# SY_HR08_MCU_TOP_V1_1.net
KiCad netlist of a schematic drawn in Altium Designer
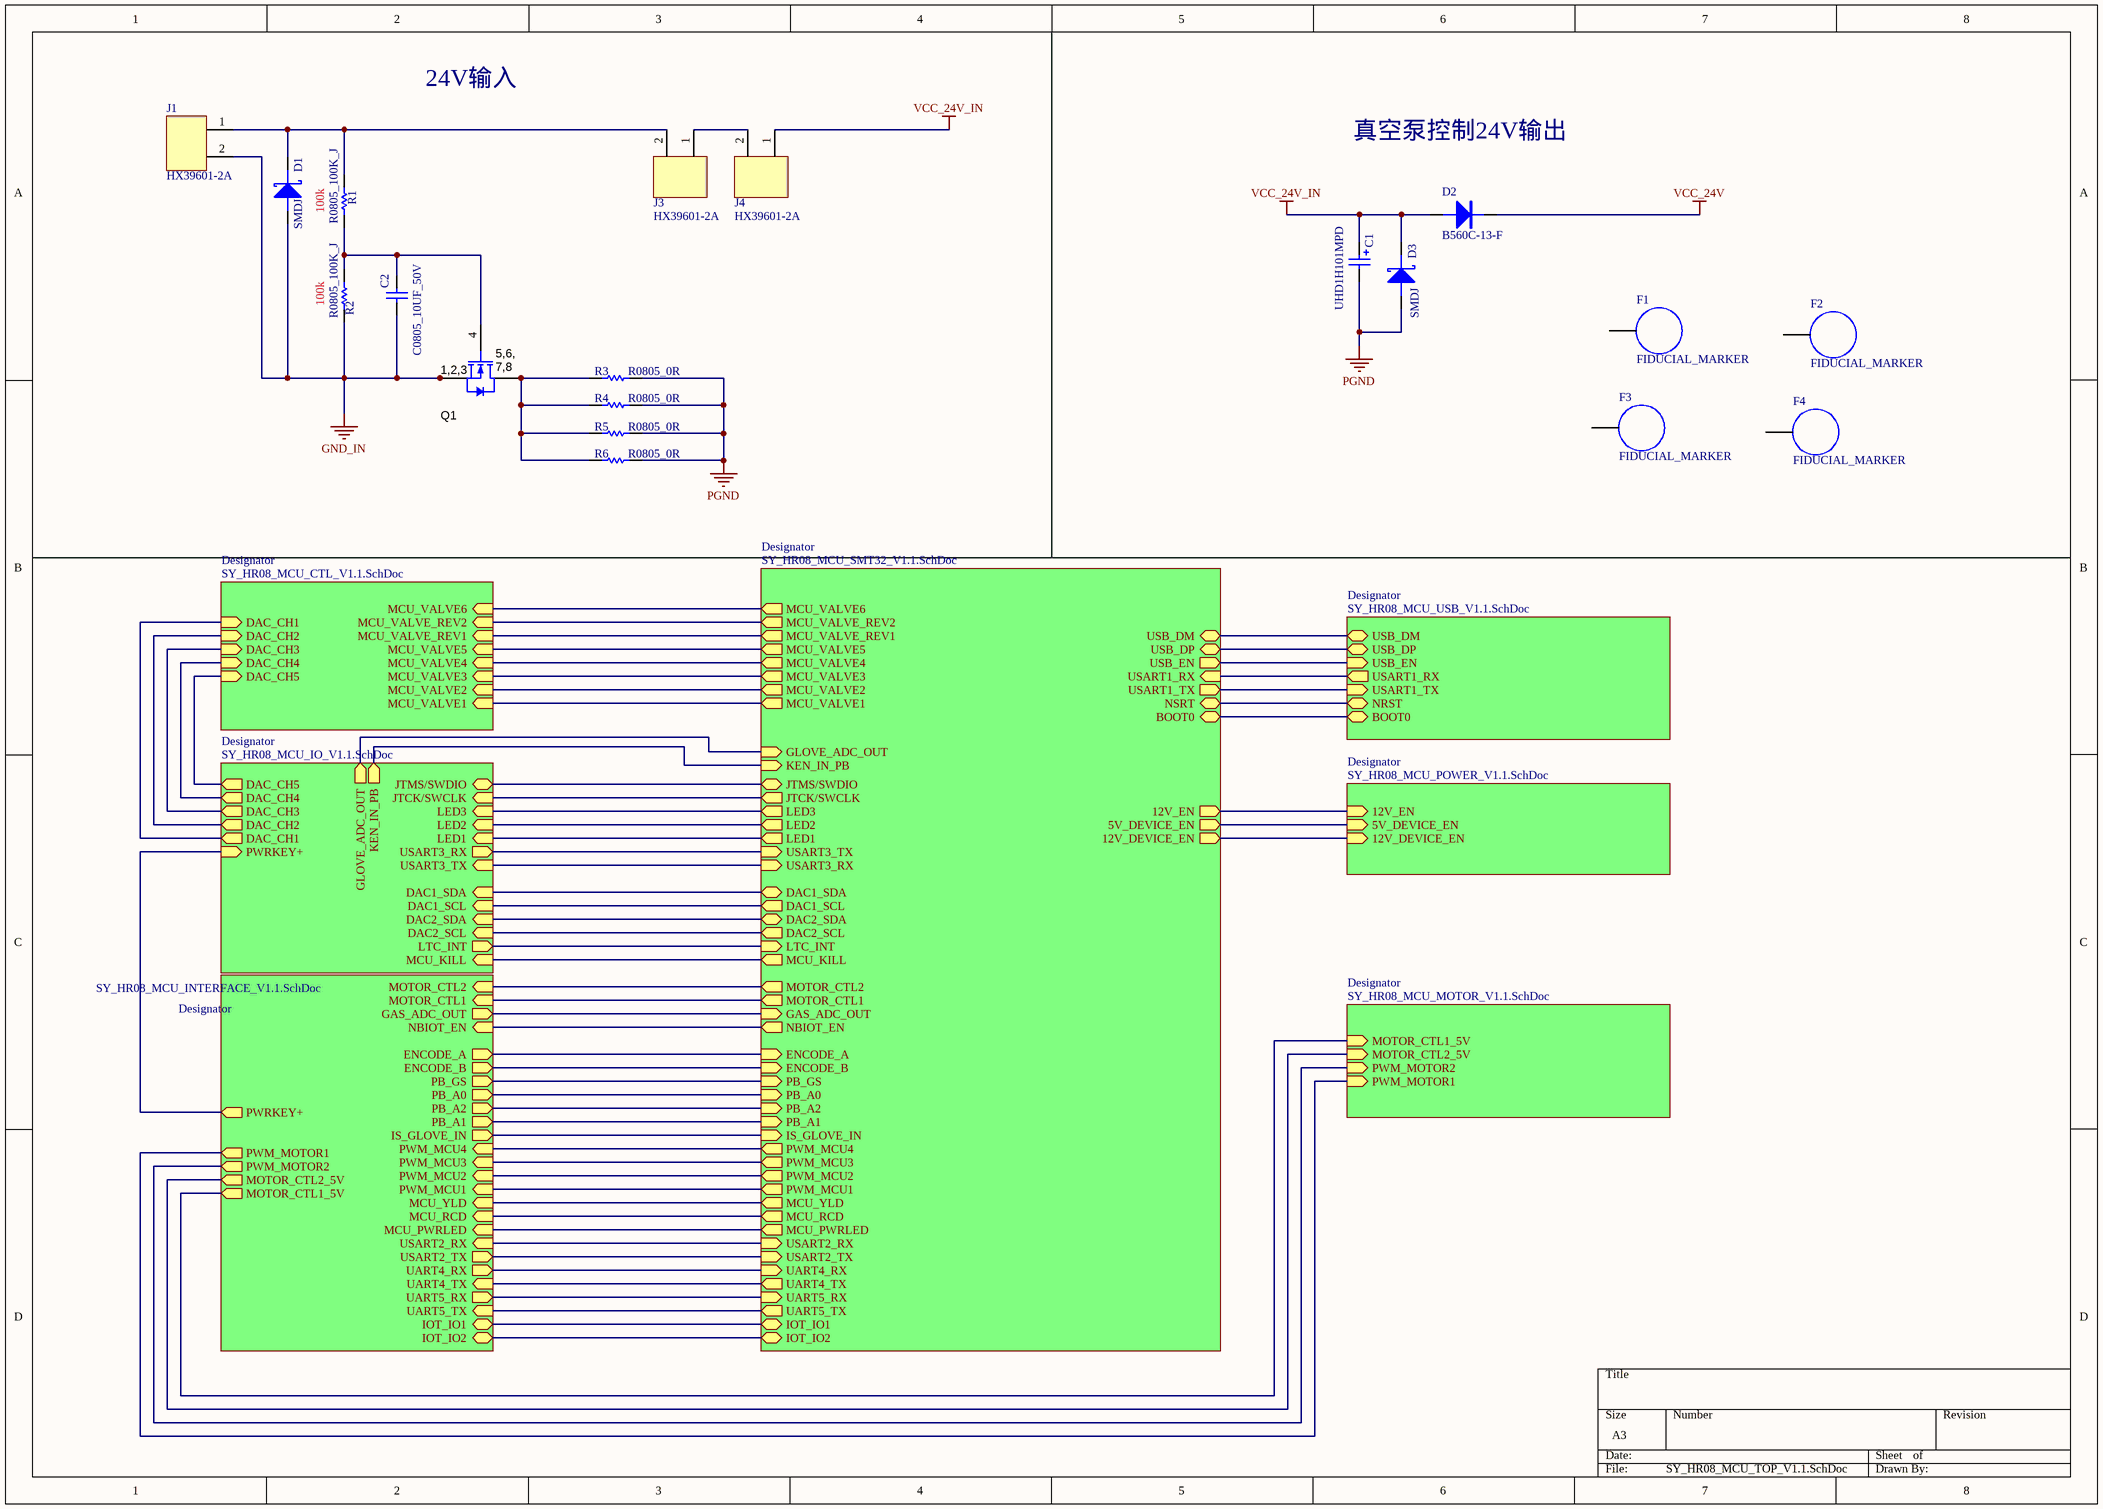
[diagram p0: SY_HR08_MCU_TOP_V1.1.SchDoc]

(export (version "E")
  (design (tool "Eeschema 10.0.6"))
  (components
    (comp (ref "C1")
      (value "UHD1H101MPD")
      (footprint "UHD1H101MPD")
      (description "铝电解电容_100uF_80115_50V_20%")
      (fields (field (name "MANUFACTURER") "nichicon"))
      (libsource (lib "zhangky_sch") (part "UHD1H101MPD"))
    )
    (comp (ref "C2")
      (value "C0805_10UF_50V")
      (footprint "CAP0805-B")
      (description "电容_10uF_0805_X5R_10V_K")
      (libsource (lib "zhangky_sch") (part "C0805_10UF_10V"))
    )
    (comp (ref "D1")
      (value "SMDJ")
      (footprint "SMDJ")
      (description "防浪涌TVS VRWM=30V VBRmin=33.3 VC=48.4 IPP=62A")
      (libsource (lib "zhangky_sch") (part "SMDJ"))
    )
    (comp (ref "D2")
      (value "B560C-13-F")
      (footprint "B540C-13-F")
      (description "肖特基二极管_5A_SMC")
      (libsource (lib "zhangky_sch") (part "B560C-13-F"))
    )
    (comp (ref "D3")
      (value "SMDJ")
      (footprint "SMDJ")
      (description "防浪涌TVS VRWM=30V VBRmin=33.3 VC=48.4 IPP=62A")
      (libsource (lib "zhangky_sch") (part "SMDJ"))
    )
    (comp (ref "F1")
      (value "FIDUCIAL_MARKER")
      (footprint "FIDUCIAL_WITHPASTE")
      (libsource (lib "zhangky_sch") (part "FIDUCIAL_MARKER"))
    )
    (comp (ref "F2")
      (value "FIDUCIAL_MARKER")
      (footprint "FIDUCIAL_WITHPASTE")
      (libsource (lib "zhangky_sch") (part "FIDUCIAL_MARKER"))
    )
    (comp (ref "F3")
      (value "FIDUCIAL_MARKER")
      (footprint "FIDUCIAL_WITHPASTE")
      (libsource (lib "zhangky_sch") (part "FIDUCIAL_MARKER"))
    )
    (comp (ref "F4")
      (value "FIDUCIAL_MARKER")
      (footprint "FIDUCIAL_WITHPASTE")
      (libsource (lib "zhangky_sch") (part "FIDUCIAL_MARKER"))
    )
    (comp (ref "J1")
      (value "HX39601-2A")
      (footprint "HX39601-2A")
      (description "HX39601-2A 3.96mm")
      (libsource (lib "zhangky_sch") (part "HX39601-2A"))
    )
    (comp (ref "J3")
      (value "HX39601-2A")
      (footprint "HX39601-2A")
      (description "HX39601-2A 3.96mm")
      (libsource (lib "zhangky_sch") (part "HX39601-2A"))
    )
    (comp (ref "J4")
      (value "HX39601-2A")
      (footprint "HX39601-2A")
      (description "HX39601-2A 3.96mm")
      (libsource (lib "zhangky_sch") (part "HX39601-2A"))
    )
    (comp (ref "Q1")
      (value "CSD18533Q5A")
      (footprint "CSD18533Q5A")
      (description "MOSFET, N-CH, 60V, 172A, SON 5x6mm")
      (libsource (lib "zhangky_sch") (part "CSD18532Q5B"))
    )
    (comp (ref "R1")
      (value "R0805_100K_J")
      (footprint "RES0805")
      (description "电阻0R(0805-0.125W-J)")
      (libsource (lib "zhangky_sch") (part "R0805_0R"))
    )
    (comp (ref "R2")
      (value "R0805_100K_J")
      (footprint "RES0805")
      (description "电阻0R(0805-0.125W-J)")
      (libsource (lib "zhangky_sch") (part "R0805_0R"))
    )
    (comp (ref "R3")
      (value "R0805_0R")
      (footprint "RES0805")
      (description "电阻0R(0805-0.125W-J)")
      (libsource (lib "zhangky_sch") (part "R0805_0R"))
    )
    (comp (ref "R4")
      (value "R0805_0R")
      (footprint "RES0805")
      (description "电阻0R(0805-0.125W-J)")
      (libsource (lib "zhangky_sch") (part "R0805_0R"))
    )
    (comp (ref "R5")
      (value "R0805_0R")
      (footprint "RES0805")
      (description "电阻0R(0805-0.125W-J)")
      (libsource (lib "zhangky_sch") (part "R0805_0R"))
    )
    (comp (ref "R6")
      (value "R0805_0R")
      (footprint "RES0805")
      (description "电阻0R(0805-0.125W-J)")
      (libsource (lib "zhangky_sch") (part "R0805_0R"))
    )
  )
  (nets
    (net (code "70") (name "GND_IN") (class "Default")
      (node (ref "C2") (pin "1") (pinfunction "1_1") (pintype "passive"))
      (node (ref "D1") (pin "1") (pinfunction "1_1") (pintype "passive"))
      (node (ref "J1") (pin "2") (pinfunction "2_2") (pintype "passive"))
      (node (ref "Q1") (pin "1") (pinfunction "S_1") (pintype "passive"))
      (node (ref "Q1") (pin "2") (pinfunction "S_2") (pintype "passive"))
      (node (ref "Q1") (pin "3") (pinfunction "S_3") (pintype "passive"))
      (node (ref "R2") (pin "1") (pinfunction "1_1") (pintype "passive"))
    )
    (net (code "71") (name "Net-(D1-Pad2)") (class "Default")
      (node (ref "D1") (pin "2") (pinfunction "2_2") (pintype "passive"))
      (node (ref "J1") (pin "1") (pinfunction "1_1") (pintype "passive"))
      (node (ref "J3") (pin "2") (pinfunction "2_2") (pintype "passive"))
      (node (ref "R1") (pin "2") (pinfunction "2_2") (pintype "passive"))
    )
    (net (code "72") (name "Net-(J3-Pad1)") (class "Default")
      (node (ref "J3") (pin "1") (pinfunction "1_1") (pintype "passive"))
      (node (ref "J4") (pin "2") (pinfunction "2_2") (pintype "passive"))
    )
    (net (code "73") (name "Net-(Q1-D-Pad5)") (class "Default")
      (node (ref "Q1") (pin "5") (pinfunction "D_5") (pintype "passive"))
      (node (ref "Q1") (pin "6") (pinfunction "D_6") (pintype "passive"))
      (node (ref "Q1") (pin "7") (pinfunction "D_7") (pintype "passive"))
      (node (ref "Q1") (pin "8") (pinfunction "D_8") (pintype "passive"))
      (node (ref "R3") (pin "1") (pinfunction "1_1") (pintype "passive"))
      (node (ref "R4") (pin "1") (pinfunction "1_1") (pintype "passive"))
      (node (ref "R5") (pin "1") (pinfunction "1_1") (pintype "passive"))
      (node (ref "R6") (pin "1") (pinfunction "1_1") (pintype "passive"))
    )
    (net (code "74") (name "Net-(Q1-G)") (class "Default")
      (node (ref "C2") (pin "2") (pinfunction "2_2") (pintype "passive"))
      (node (ref "Q1") (pin "4") (pinfunction "G_4") (pintype "passive"))
      (node (ref "R1") (pin "1") (pinfunction "1_1") (pintype "passive"))
      (node (ref "R2") (pin "2") (pinfunction "2_2") (pintype "passive"))
    )
    (net (code "75") (name "PGND") (class "Default")
      (node (ref "C1") (pin "2") (pinfunction "2_2") (pintype "passive"))
      (node (ref "D3") (pin "1") (pinfunction "1_1") (pintype "passive"))
      (node (ref "R3") (pin "2") (pinfunction "2_2") (pintype "passive"))
      (node (ref "R4") (pin "2") (pinfunction "2_2") (pintype "passive"))
      (node (ref "R5") (pin "2") (pinfunction "2_2") (pintype "passive"))
      (node (ref "R6") (pin "2") (pinfunction "2_2") (pintype "passive"))
    )
    (net (code "76") (name "VCC_24V") (class "Default")
      (node (ref "D2") (pin "1") (pinfunction "1_1") (pintype "passive"))
    )
    (net (code "77") (name "VCC_24V_IN") (class "Default")
      (node (ref "C1") (pin "1") (pinfunction "1_1") (pintype "passive"))
      (node (ref "D2") (pin "2") (pinfunction "2_2") (pintype "passive"))
      (node (ref "D3") (pin "2") (pinfunction "2_2") (pintype "passive"))
      (node (ref "J4") (pin "1") (pinfunction "1_1") (pintype "passive"))
    )
    (net (code "78") (name "unconnected-(F1-Pad1)") (class "Default")
      (node (ref "F1") (pin "1") (pinfunction "1_1") (pintype "passive"))
    )
    (net (code "79") (name "unconnected-(F2-Pad1)") (class "Default")
      (node (ref "F2") (pin "1") (pinfunction "1_1") (pintype "passive"))
    )
    (net (code "80") (name "unconnected-(F3-Pad1)") (class "Default")
      (node (ref "F3") (pin "1") (pinfunction "1_1") (pintype "passive"))
    )
    (net (code "81") (name "unconnected-(F4-Pad1)") (class "Default")
      (node (ref "F4") (pin "1") (pinfunction "1_1") (pintype "passive"))
    )
  )
)
